# HD301_driver.net
KiCad netlist of a schematic drawn in Altium Designer
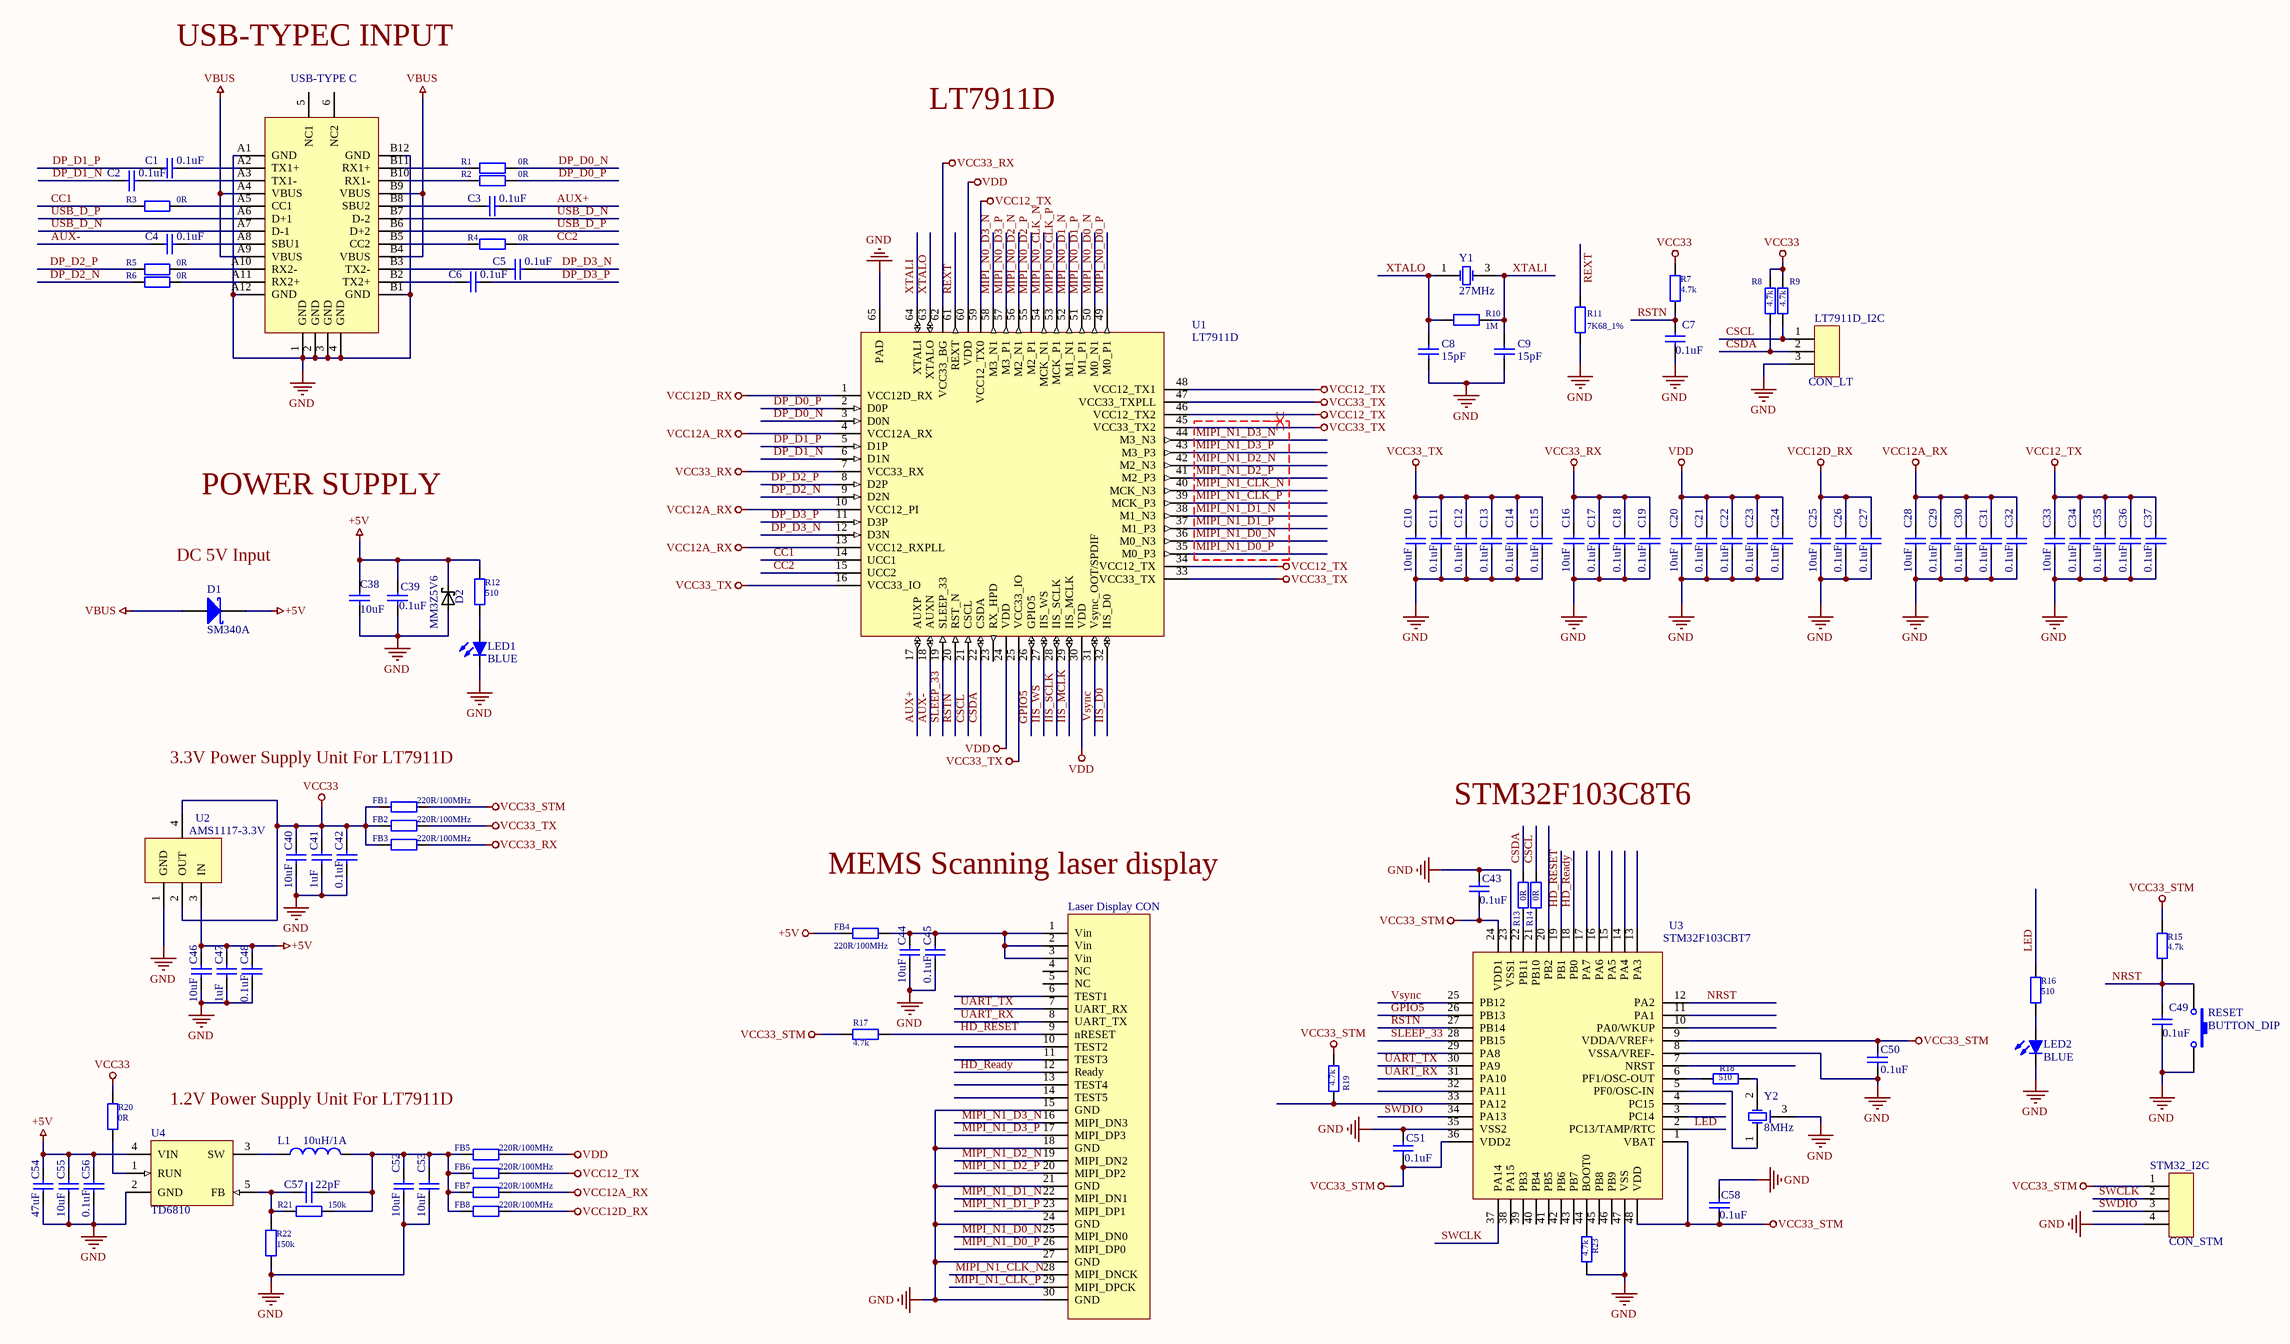
[diagram p0: HD301_driver.SchDoc]

(export (version "E")
  (design (tool "Eeschema 10.0.6"))
  (components
    (comp (ref "C1")
      (value "0.1uF")
      (footprint "0402-C")
      (description "Capacitor")
      (libsource (lib "Miscellaneous Devices") (part "Cap"))
    )
    (comp (ref "C2")
      (value "0.1uF")
      (footprint "0402-C")
      (description "Capacitor")
      (libsource (lib "Miscellaneous Devices") (part "Cap"))
    )
    (comp (ref "C3")
      (value "0.1uF")
      (footprint "0402-C")
      (description "Capacitor")
      (libsource (lib "Miscellaneous Devices") (part "Cap"))
    )
    (comp (ref "C4")
      (value "0.1uF")
      (footprint "0402-C")
      (description "Capacitor")
      (libsource (lib "Miscellaneous Devices") (part "Cap"))
    )
    (comp (ref "C5")
      (value "0.1uF")
      (footprint "0402-C")
      (description "Capacitor")
      (libsource (lib "Miscellaneous Devices") (part "Cap"))
    )
    (comp (ref "C6")
      (value "0.1uF")
      (footprint "0402-C")
      (description "Capacitor")
      (libsource (lib "Miscellaneous Devices") (part "Cap"))
    )
    (comp (ref "C7")
      (value "0.1uF")
      (footprint "0402-C")
      (description "Capacitor")
      (libsource (lib "Miscellaneous Devices") (part "Cap"))
    )
    (comp (ref "C8")
      (value "15pF")
      (footprint "0402-C")
      (description "Capacitor")
      (libsource (lib "Miscellaneous Devices") (part "Cap"))
    )
    (comp (ref "C9")
      (value "15pF")
      (footprint "0402-C")
      (description "Capacitor")
      (libsource (lib "Miscellaneous Devices") (part "Cap"))
    )
    (comp (ref "C10")
      (value "10uF")
      (footprint "0603-C")
      (description "Capacitor")
      (libsource (lib "Miscellaneous Devices") (part "Cap"))
    )
    (comp (ref "C11")
      (value "0.1uF")
      (footprint "0402-C")
      (description "Capacitor")
      (libsource (lib "Miscellaneous Devices") (part "Cap"))
    )
    (comp (ref "C12")
      (value "0.1uF")
      (footprint "0402-C")
      (description "Capacitor")
      (libsource (lib "Miscellaneous Devices") (part "Cap"))
    )
    (comp (ref "C13")
      (value "0.1uF")
      (footprint "0402-C")
      (description "Capacitor")
      (libsource (lib "Miscellaneous Devices") (part "Cap"))
    )
    (comp (ref "C14")
      (value "0.1uF")
      (footprint "0402-C")
      (description "Capacitor")
      (libsource (lib "Miscellaneous Devices") (part "Cap"))
    )
    (comp (ref "C15")
      (value "0.1uF")
      (footprint "0402-C")
      (description "Capacitor")
      (libsource (lib "Miscellaneous Devices") (part "Cap"))
    )
    (comp (ref "C16")
      (value "10uF")
      (footprint "0603-C")
      (description "Capacitor")
      (libsource (lib "Miscellaneous Devices") (part "Cap"))
    )
    (comp (ref "C17")
      (value "0.1uF")
      (footprint "0402-C")
      (description "Capacitor")
      (libsource (lib "Miscellaneous Devices") (part "Cap"))
    )
    (comp (ref "C18")
      (value "0.1uF")
      (footprint "0402-C")
      (description "Capacitor")
      (libsource (lib "Miscellaneous Devices") (part "Cap"))
    )
    (comp (ref "C19")
      (value "0.1uF")
      (footprint "0402-C")
      (description "Capacitor")
      (libsource (lib "Miscellaneous Devices") (part "Cap"))
    )
    (comp (ref "C20")
      (value "10uF")
      (footprint "0603-C")
      (description "Capacitor")
      (libsource (lib "Miscellaneous Devices") (part "Cap"))
    )
    (comp (ref "C21")
      (value "0.1uF")
      (footprint "0402-C")
      (description "Capacitor")
      (libsource (lib "Miscellaneous Devices") (part "Cap"))
    )
    (comp (ref "C22")
      (value "0.1uF")
      (footprint "0402-C")
      (description "Capacitor")
      (libsource (lib "Miscellaneous Devices") (part "Cap"))
    )
    (comp (ref "C23")
      (value "0.1uF")
      (footprint "0402-C")
      (description "Capacitor")
      (libsource (lib "Miscellaneous Devices") (part "Cap"))
    )
    (comp (ref "C24")
      (value "0.1uF")
      (footprint "0402-C")
      (description "Capacitor")
      (libsource (lib "Miscellaneous Devices") (part "Cap"))
    )
    (comp (ref "C25")
      (value "10uF")
      (footprint "0603-C")
      (description "Capacitor")
      (libsource (lib "Miscellaneous Devices") (part "Cap"))
    )
    (comp (ref "C26")
      (value "0.1uF")
      (footprint "0402-C")
      (description "Capacitor")
      (libsource (lib "Miscellaneous Devices") (part "Cap"))
    )
    (comp (ref "C27")
      (value "0.1uF")
      (footprint "0402-C")
      (description "Capacitor")
      (libsource (lib "Miscellaneous Devices") (part "Cap"))
    )
    (comp (ref "C28")
      (value "10uF")
      (footprint "0603-C")
      (description "Capacitor")
      (libsource (lib "Miscellaneous Devices") (part "Cap"))
    )
    (comp (ref "C29")
      (value "0.1uF")
      (footprint "0402-C")
      (description "Capacitor")
      (libsource (lib "Miscellaneous Devices") (part "Cap"))
    )
    (comp (ref "C30")
      (value "0.1uF")
      (footprint "0402-C")
      (description "Capacitor")
      (libsource (lib "Miscellaneous Devices") (part "Cap"))
    )
    (comp (ref "C31")
      (value "0.1uF")
      (footprint "0402-C")
      (description "Capacitor")
      (libsource (lib "Miscellaneous Devices") (part "Cap"))
    )
    (comp (ref "C32")
      (value "0.1uF")
      (footprint "0402-C")
      (description "Capacitor")
      (libsource (lib "Miscellaneous Devices") (part "Cap"))
    )
    (comp (ref "C33")
      (value "10uF")
      (footprint "0603-C")
      (description "Capacitor")
      (libsource (lib "Miscellaneous Devices") (part "Cap"))
    )
    (comp (ref "C34")
      (value "0.1uF")
      (footprint "0402-C")
      (description "Capacitor")
      (libsource (lib "Miscellaneous Devices") (part "Cap"))
    )
    (comp (ref "C35")
      (value "0.1uF")
      (footprint "0402-C")
      (description "Capacitor")
      (libsource (lib "Miscellaneous Devices") (part "Cap"))
    )
    (comp (ref "C36")
      (value "0.1uF")
      (footprint "0402-C")
      (description "Capacitor")
      (libsource (lib "Miscellaneous Devices") (part "Cap"))
    )
    (comp (ref "C37")
      (value "0.1uF")
      (footprint "0402-C")
      (description "Capacitor")
      (libsource (lib "Miscellaneous Devices") (part "Cap"))
    )
    (comp (ref "C38")
      (value "10uF")
      (footprint "0603-C")
      (description "Capacitor")
      (libsource (lib "Miscellaneous Devices") (part "Cap"))
    )
    (comp (ref "C39")
      (value "0.1uF")
      (footprint "0402-C")
      (description "Capacitor")
      (libsource (lib "Miscellaneous Devices") (part "Cap"))
    )
    (comp (ref "C40")
      (value "10uF")
      (footprint "0603-C")
      (description "Capacitor")
      (libsource (lib "Miscellaneous Devices") (part "Cap"))
    )
    (comp (ref "C41")
      (value "1uF")
      (footprint "0603-C")
      (description "Capacitor")
      (libsource (lib "Miscellaneous Devices") (part "Cap"))
    )
    (comp (ref "C42")
      (value "0.1uF")
      (footprint "0402-C")
      (description "Capacitor")
      (libsource (lib "Miscellaneous Devices") (part "Cap"))
    )
    (comp (ref "C43")
      (value "0.1uF")
      (footprint "0402-C")
      (description "Capacitor")
      (libsource (lib "Miscellaneous Devices") (part "Cap"))
    )
    (comp (ref "C44")
      (value "10uF")
      (footprint "0603-C")
      (description "Capacitor")
      (libsource (lib "Miscellaneous Devices") (part "Cap"))
    )
    (comp (ref "C45")
      (value "0.1uF")
      (footprint "0402-C")
      (description "Capacitor")
      (libsource (lib "Miscellaneous Devices") (part "Cap"))
    )
    (comp (ref "C46")
      (value "10uF")
      (footprint "0603-C")
      (description "Capacitor")
      (libsource (lib "Miscellaneous Devices") (part "Cap"))
    )
    (comp (ref "C47")
      (value "1uF")
      (footprint "0603-C")
      (description "Capacitor")
      (libsource (lib "Miscellaneous Devices") (part "Cap"))
    )
    (comp (ref "C48")
      (value "0.1uF")
      (footprint "0402-C")
      (description "Capacitor")
      (libsource (lib "Miscellaneous Devices") (part "Cap"))
    )
    (comp (ref "C49")
      (value "0.1uF")
      (footprint "0402-C")
      (description "Capacitor")
      (libsource (lib "Miscellaneous Devices") (part "Cap"))
    )
    (comp (ref "C50")
      (value "0.1uF")
      (footprint "0402-C")
      (description "Capacitor")
      (libsource (lib "Miscellaneous Devices") (part "Cap"))
    )
    (comp (ref "C51")
      (value "0.1uF")
      (footprint "0402-C")
      (description "Capacitor")
      (libsource (lib "Miscellaneous Devices") (part "Cap"))
    )
    (comp (ref "C52")
      (value "10uF")
      (footprint "0603-C")
      (description "Capacitor")
      (libsource (lib "Miscellaneous Devices") (part "Cap"))
    )
    (comp (ref "C53")
      (value "10uF")
      (footprint "0603-C")
      (description "Capacitor")
      (libsource (lib "Miscellaneous Devices") (part "Cap"))
    )
    (comp (ref "C54")
      (value "47uF")
      (footprint "1206-C")
      (description "Capacitor")
      (libsource (lib "Miscellaneous Devices") (part "Cap"))
    )
    (comp (ref "C55")
      (value "10uF")
      (footprint "0603-C")
      (description "Capacitor")
      (libsource (lib "Miscellaneous Devices") (part "Cap"))
    )
    (comp (ref "C56")
      (value "0.1uF")
      (footprint "0402-C")
      (description "Capacitor")
      (libsource (lib "Miscellaneous Devices") (part "Cap"))
    )
    (comp (ref "C57")
      (value "22pF")
      (footprint "0402-C")
      (description "Capacitor")
      (libsource (lib "Miscellaneous Devices") (part "Cap"))
    )
    (comp (ref "C58")
      (value "0.1uF")
      (footprint "0402-C")
      (description "Capacitor")
      (libsource (lib "Miscellaneous Devices") (part "Cap"))
    )
    (comp (ref "D1")
      (value "SM340A")
      (footprint "SM340A_DO-214AC")
      (description "Schottky Rectifier")
      (libsource (lib "Miscellaneous Devices") (part "Diode 10TQ035"))
    )
    (comp (ref "D2")
      (value "MM3Z5V6")
      (footprint "PDZ_B-SOD323")
      (fields (field (name "MP") "BAT46W") (field (name "MF") "Diotec"))
      (libsource (lib "MySchLib") (part "BAT46W"))
    )
    (comp (ref "FB1")
      (value "220R/100MHz")
      (footprint "0603-FB")
      (description "Resistor")
      (libsource (lib "") (part "Res2_3"))
    )
    (comp (ref "FB2")
      (value "220R/100MHz")
      (footprint "0603-FB")
      (description "Resistor")
      (libsource (lib "") (part "Res2_3"))
    )
    (comp (ref "FB3")
      (value "220R/100MHz")
      (footprint "0603-FB")
      (description "Resistor")
      (libsource (lib "") (part "Res2_3"))
    )
    (comp (ref "FB4")
      (value "220R/100MHz")
      (footprint "0603-FB")
      (description "Resistor")
      (libsource (lib "") (part "Res2_3"))
    )
    (comp (ref "FB5")
      (value "220R/100MHz")
      (footprint "0603-FB")
      (description "Resistor")
      (libsource (lib "") (part "Res2_3"))
    )
    (comp (ref "FB6")
      (value "220R/100MHz")
      (footprint "0603-FB")
      (description "Resistor")
      (libsource (lib "") (part "Res2_3"))
    )
    (comp (ref "FB7")
      (value "220R/100MHz")
      (footprint "0603-FB")
      (description "Resistor")
      (libsource (lib "") (part "Res2_3"))
    )
    (comp (ref "FB8")
      (value "220R/100MHz")
      (footprint "0603-FB")
      (description "Resistor")
      (libsource (lib "") (part "Res2_3"))
    )
    (comp (ref "L1")
      (value "10uH/1A")
      (footprint "Inductor_LPS4018-103MR")
      (description "Inductor")
      (libsource (lib "Miscellaneous Devices") (part "Inductor"))
    )
    (comp (ref "Laser Display CON")
      (value "MIPI-DSI")
      (footprint "50696-030-0-M")
      (libsource (lib "MySchLib") (part "MIPI-DSI"))
    )
    (comp (ref "LED1")
      (value "BLUE")
      (footprint "SMD_LED(0603)")
      (description "Typical RED GaAs LED")
      (libsource (lib "MySchLib") (part "LED1"))
    )
    (comp (ref "LED2")
      (value "BLUE")
      (footprint "SMD_LED(0603)")
      (description "Typical RED GaAs LED")
      (libsource (lib "MySchLib") (part "LED1"))
    )
    (comp (ref "LT7911D_I2C")
      (value "CON_LT")
      (footprint "Header-Female-2.54*3")
      (libsource (lib "MySchLib") (part "3PinConnector"))
    )
    (comp (ref "R1")
      (value "0R")
      (footprint "0402-R")
      (description "Resistor")
      (libsource (lib "") (part "Res2_2"))
    )
    (comp (ref "R2")
      (value "0R")
      (footprint "0402-R")
      (description "Resistor")
      (libsource (lib "") (part "Res2_2"))
    )
    (comp (ref "R3")
      (value "0R")
      (footprint "0402-R")
      (description "Resistor")
      (libsource (lib "") (part "Res2_2"))
    )
    (comp (ref "R4")
      (value "0R")
      (footprint "0402-R")
      (description "Resistor")
      (libsource (lib "") (part "Res2_2"))
    )
    (comp (ref "R5")
      (value "0R")
      (footprint "0402-R")
      (description "Resistor")
      (libsource (lib "") (part "Res2_2"))
    )
    (comp (ref "R6")
      (value "0R")
      (footprint "0402-R")
      (description "Resistor")
      (libsource (lib "") (part "Res2_2"))
    )
    (comp (ref "R7")
      (value "4.7k")
      (footprint "0402-R")
      (description "Resistor")
      (libsource (lib "") (part "Res2_1"))
    )
    (comp (ref "R8")
      (value "4.7k")
      (footprint "0402-R")
      (description "Resistor")
      (libsource (lib "Miscellaneous Devices") (part "Res2"))
    )
    (comp (ref "R9")
      (value "4.7k")
      (footprint "0402-R")
      (description "Resistor")
      (libsource (lib "Miscellaneous Devices") (part "Res2"))
    )
    (comp (ref "R10")
      (value "1M")
      (footprint "0402-R")
      (description "Resistor")
      (libsource (lib "") (part "Res2_3"))
    )
    (comp (ref "R11")
      (value "7K68_1%")
      (footprint "0402-R")
      (description "Resistor")
      (libsource (lib "Miscellaneous Devices") (part "Res2"))
    )
    (comp (ref "R12")
      (value "510")
      (footprint "0402-R")
      (description "Resistor")
      (libsource (lib "") (part "Res2_1"))
    )
    (comp (ref "R13")
      (value "0R")
      (footprint "0402-R")
      (description "Resistor")
      (libsource (lib "Miscellaneous Devices") (part "Res2"))
    )
    (comp (ref "R14")
      (value "0R")
      (footprint "0402-R")
      (description "Resistor")
      (libsource (lib "Miscellaneous Devices") (part "Res2"))
    )
    (comp (ref "R15")
      (value "4.7k")
      (footprint "0402-R")
      (description "Resistor")
      (libsource (lib "") (part "Res2_1"))
    )
    (comp (ref "R16")
      (value "510")
      (footprint "0402-R")
      (description "Resistor")
      (libsource (lib "") (part "Res2_1"))
    )
    (comp (ref "R17")
      (value "4.7k")
      (footprint "0402-R")
      (description "Resistor")
      (libsource (lib "") (part "Res2_2"))
    )
    (comp (ref "R18")
      (value "510")
      (footprint "0402-R")
      (description "Resistor")
      (libsource (lib "") (part "Res2_3"))
    )
    (comp (ref "R19")
      (value "4.7k")
      (footprint "0402-R")
      (description "Resistor")
      (libsource (lib "Miscellaneous Devices") (part "Res2"))
    )
    (comp (ref "R20")
      (value "0R")
      (footprint "0402-R")
      (description "Resistor")
      (libsource (lib "") (part "Res2_1"))
    )
    (comp (ref "R21")
      (value "150k")
      (footprint "0402-R")
      (description "Resistor")
      (libsource (lib "") (part "Res2_3"))
    )
    (comp (ref "R22")
      (value "150k")
      (footprint "0402-R")
      (description "Resistor")
      (libsource (lib "Miscellaneous Devices") (part "Res2"))
    )
    (comp (ref "R23")
      (value "4.7k")
      (footprint "0402-R")
      (description "Resistor")
      (libsource (lib "Miscellaneous Devices") (part "Res2"))
    )
    (comp (ref "RESET")
      (value "BUTTON_DIP")
      (footprint "Push button_mini(2 pin)")
      (description "Switch")
      (libsource (lib "Miscellaneous Devices") (part "SW-PB"))
    )
    (comp (ref "STM32_I2C")
      (value "CON_STM")
      (footprint "Header-Female-2.54*4")
      (libsource (lib "MySchLib") (part "4PinConnector"))
    )
    (comp (ref "U1")
      (value "LT7911D")
      (footprint "QFN64_EPAD")
      (description "USB/MIPI port converter")
      (libsource (lib "MySchLib") (part "LT7911D"))
    )
    (comp (ref "U2")
      (value "AMS1117-3.3V")
      (footprint "AMS1117_SOT-223_4")
      (description "3.3V Voltage Regulator")
      (libsource (lib "MySchLib") (part "AMS1117-3.3V"))
    )
    (comp (ref "U3")
      (value "STM32F103CBT7")
      (footprint "LQFP48-7mm*7mm")
      (description "32bit MCU")
      (libsource (lib "MySchLib") (part "STM32F303CBT7"))
    )
    (comp (ref "U4")
      (value "TD6810")
      (footprint "TD6810_SOT23-5")
      (description "voltage regulater")
      (libsource (lib "MySchLib") (part "TD6810"))
    )
    (comp (ref "USB-TYPE C")
      (value "USB-TYPEC")
      (footprint "USB_TYPEC_RECEPTACLE_DIP")
      (description "USB-TYPEC INPUT")
      (libsource (lib "MySchLib") (part "USB-TYPEC"))
    )
    (comp (ref "Y1")
      (value "27MHz")
      (footprint "CRY_3225")
      (description "Crystal Oscillator")
      (libsource (lib "MySchLib") (part "XTAL_2"))
    )
    (comp (ref "Y2")
      (value "8MHz")
      (footprint "Resonator_mini")
      (description "Crystal Oscillator")
      (libsource (lib "MySchLib") (part "XTAL"))
    )
  )
  (nets
    (net (code "1") (name "+5V") (class "Default")
      (node (ref "C38") (pin "1") (pinfunction "1_1") (pintype "passive"))
      (node (ref "C39") (pin "2") (pinfunction "2_2") (pintype "passive"))
      (node (ref "C46") (pin "1") (pinfunction "1_1") (pintype "passive"))
      (node (ref "C47") (pin "1") (pinfunction "1_1") (pintype "passive"))
      (node (ref "C48") (pin "1") (pinfunction "1_1") (pintype "passive"))
      (node (ref "C54") (pin "1") (pinfunction "1_1") (pintype "passive"))
      (node (ref "C55") (pin "1") (pinfunction "1_1") (pintype "passive"))
      (node (ref "C56") (pin "1") (pinfunction "1_1") (pintype "passive"))
      (node (ref "D1") (pin "C") (pinfunction "C_C") (pintype "passive"))
      (node (ref "D2") (pin "C") (pinfunction "C_C") (pintype "passive"))
      (node (ref "FB4") (pin "1") (pinfunction "1_1") (pintype "passive"))
      (node (ref "R12") (pin "1") (pinfunction "1_1") (pintype "passive"))
      (node (ref "U2") (pin "3") (pinfunction "IN_3") (pintype "passive"))
      (node (ref "U4") (pin "4") (pinfunction "VIN_4") (pintype "passive"))
    )
    (net (code "2") (name "/AUX+") (class "Default")
      (node (ref "C3") (pin "2") (pinfunction "2_2") (pintype "passive"))
      (node (ref "U1") (pin "17") (pinfunction "AUXP_17") (pintype "bidirectional"))
    )
    (net (code "3") (name "/AUX-") (class "Default")
      (node (ref "C4") (pin "2") (pinfunction "2_2") (pintype "passive"))
      (node (ref "U1") (pin "18") (pinfunction "AUXN_18") (pintype "bidirectional"))
    )
    (net (code "4") (name "/CC1") (class "Default")
      (node (ref "R3") (pin "2") (pinfunction "2_2") (pintype "passive"))
      (node (ref "U1") (pin "14") (pinfunction "UCC1_14") (pintype "power_in"))
    )
    (net (code "5") (name "/CC2") (class "Default")
      (node (ref "R4") (pin "1") (pinfunction "1_1") (pintype "passive"))
      (node (ref "U1") (pin "15") (pinfunction "UCC2_15") (pintype "power_in"))
    )
    (net (code "6") (name "/CSCL") (class "Default")
      (node (ref "LT7911D_I2C") (pin "1") (pinfunction "1_1") (pintype "passive"))
      (node (ref "R14") (pin "2") (pinfunction "2_2") (pintype "passive"))
      (node (ref "R9") (pin "1") (pinfunction "1_1") (pintype "passive"))
      (node (ref "U1") (pin "21") (pinfunction "CSCL_21") (pintype "input"))
    )
    (net (code "7") (name "/CSDA") (class "Default")
      (node (ref "LT7911D_I2C") (pin "2") (pinfunction "2_2") (pintype "passive"))
      (node (ref "R13") (pin "2") (pinfunction "2_2") (pintype "passive"))
      (node (ref "R8") (pin "1") (pinfunction "1_1") (pintype "passive"))
      (node (ref "U1") (pin "22") (pinfunction "CSDA_22") (pintype "bidirectional"))
    )
    (net (code "8") (name "/DP_D0_N") (class "Default")
      (node (ref "R1") (pin "1") (pinfunction "1_1") (pintype "passive"))
      (node (ref "U1") (pin "3") (pinfunction "D0N_3") (pintype "input"))
    )
    (net (code "9") (name "/DP_D0_P") (class "Default")
      (node (ref "R2") (pin "1") (pinfunction "1_1") (pintype "passive"))
      (node (ref "U1") (pin "2") (pinfunction "D0P_2") (pintype "input"))
    )
    (net (code "10") (name "/DP_D1_N") (class "Default")
      (node (ref "C2") (pin "2") (pinfunction "2_2") (pintype "passive"))
      (node (ref "U1") (pin "6") (pinfunction "D1N_6") (pintype "input"))
    )
    (net (code "11") (name "/DP_D1_P") (class "Default")
      (node (ref "C1") (pin "2") (pinfunction "2_2") (pintype "passive"))
      (node (ref "U1") (pin "5") (pinfunction "D1P_5") (pintype "input"))
    )
    (net (code "12") (name "/DP_D2_N") (class "Default")
      (node (ref "R6") (pin "2") (pinfunction "2_2") (pintype "passive"))
      (node (ref "U1") (pin "9") (pinfunction "D2N_9") (pintype "input"))
    )
    (net (code "13") (name "/DP_D2_P") (class "Default")
      (node (ref "R5") (pin "2") (pinfunction "2_2") (pintype "passive"))
      (node (ref "U1") (pin "8") (pinfunction "D2P_8") (pintype "input"))
    )
    (net (code "14") (name "/DP_D3_N") (class "Default")
      (node (ref "C5") (pin "2") (pinfunction "2_2") (pintype "passive"))
      (node (ref "U1") (pin "12") (pinfunction "D3N_12") (pintype "input"))
    )
    (net (code "15") (name "/DP_D3_P") (class "Default")
      (node (ref "C6") (pin "2") (pinfunction "2_2") (pintype "passive"))
      (node (ref "U1") (pin "11") (pinfunction "D3P_11") (pintype "input"))
    )
    (net (code "16") (name "/GPIO5") (class "Default")
      (node (ref "U1") (pin "26") (pinfunction "GPIO5_26") (pintype "bidirectional"))
      (node (ref "U3") (pin "26") (pinfunction "PB13_26") (pintype "power_in"))
    )
    (net (code "17") (name "/HD_RESET") (class "Default")
      (node (ref "Laser Display CON") (pin "9") (pinfunction "nRESET_9") (pintype "passive"))
      (node (ref "R17") (pin "1") (pinfunction "1_1") (pintype "passive"))
      (node (ref "U3") (pin "19") (pinfunction "PB1_19") (pintype "power_in"))
    )
    (net (code "18") (name "/HD_Ready") (class "Default")
      (node (ref "Laser Display CON") (pin "12") (pinfunction "Ready_12") (pintype "passive"))
      (node (ref "U3") (pin "18") (pinfunction "PB0_18") (pintype "power_in"))
    )
    (net (code "19") (name "/IIS_D0") (class "Default")
      (node (ref "U1") (pin "32") (pinfunction "IIS_D0_32") (pintype "bidirectional"))
    )
    (net (code "20") (name "/IIS_MCLK") (class "Default")
      (node (ref "U1") (pin "29") (pinfunction "IIS_MCLK_29") (pintype "bidirectional"))
    )
    (net (code "21") (name "/IIS_SCLK") (class "Default")
      (node (ref "U1") (pin "28") (pinfunction "IIS_SCLK_28") (pintype "bidirectional"))
    )
    (net (code "22") (name "/IIS_WS") (class "Default")
      (node (ref "U1") (pin "27") (pinfunction "IIS_WS_27") (pintype "bidirectional"))
    )
    (net (code "23") (name "/LED") (class "Default")
      (node (ref "R16") (pin "1") (pinfunction "1_1") (pintype "passive"))
      (node (ref "U3") (pin "2") (pinfunction "PC13/TAMP/RTC_2") (pintype "power_in"))
    )
    (net (code "24") (name "/MIPI_N0_CLK_N") (class "Default")
      (node (ref "U1") (pin "54") (pinfunction "MCK_N1_54") (pintype "output"))
    )
    (net (code "25") (name "/MIPI_N0_CLK_P") (class "Default")
      (node (ref "U1") (pin "53") (pinfunction "MCK_P1_53") (pintype "output"))
    )
    (net (code "26") (name "/MIPI_N0_D0_N") (class "Default")
      (node (ref "U1") (pin "50") (pinfunction "M0_N1_50") (pintype "output"))
    )
    (net (code "27") (name "/MIPI_N0_D0_P") (class "Default")
      (node (ref "U1") (pin "49") (pinfunction "M0_P1_49") (pintype "output"))
    )
    (net (code "28") (name "/MIPI_N0_D1_N") (class "Default")
      (node (ref "U1") (pin "52") (pinfunction "M1_N1_52") (pintype "output"))
    )
    (net (code "29") (name "/MIPI_N0_D1_P") (class "Default")
      (node (ref "U1") (pin "51") (pinfunction "M1_P1_51") (pintype "output"))
    )
    (net (code "30") (name "/MIPI_N0_D2_N") (class "Default")
      (node (ref "U1") (pin "56") (pinfunction "M2_N1_56") (pintype "output"))
    )
    (net (code "31") (name "/MIPI_N0_D2_P") (class "Default")
      (node (ref "U1") (pin "55") (pinfunction "M2_P1_55") (pintype "open_collector"))
    )
    (net (code "32") (name "/MIPI_N0_D3_N") (class "Default")
      (node (ref "U1") (pin "58") (pinfunction "M3_N1_58") (pintype "output"))
    )
    (net (code "33") (name "/MIPI_N0_D3_P") (class "Default")
      (node (ref "U1") (pin "57") (pinfunction "M3_P1_57") (pintype "output"))
    )
    (net (code "34") (name "/MIPI_N1_CLK_N") (class "Default")
      (node (ref "Laser Display CON") (pin "28") (pinfunction "MIPI_DNCK_28") (pintype "passive"))
      (node (ref "U1") (pin "40") (pinfunction "MCK_N3_40") (pintype "output"))
    )
    (net (code "35") (name "/MIPI_N1_CLK_P") (class "Default")
      (node (ref "Laser Display CON") (pin "29") (pinfunction "MIPI_DPCK_29") (pintype "passive"))
      (node (ref "U1") (pin "39") (pinfunction "MCK_P3_39") (pintype "output"))
    )
    (net (code "36") (name "/MIPI_N1_D0_N") (class "Default")
      (node (ref "Laser Display CON") (pin "25") (pinfunction "MIPI_DN0_25") (pintype "passive"))
      (node (ref "U1") (pin "36") (pinfunction "M0_N3_36") (pintype "output"))
    )
    (net (code "37") (name "/MIPI_N1_D0_P") (class "Default")
      (node (ref "Laser Display CON") (pin "26") (pinfunction "MIPI_DP0_26") (pintype "passive"))
      (node (ref "U1") (pin "35") (pinfunction "M0_P3_35") (pintype "output"))
    )
    (net (code "38") (name "/MIPI_N1_D1_N") (class "Default")
      (node (ref "Laser Display CON") (pin "22") (pinfunction "MIPI_DN1_22") (pintype "passive"))
      (node (ref "U1") (pin "38") (pinfunction "M1_N3_38") (pintype "output"))
    )
    (net (code "39") (name "/MIPI_N1_D1_P") (class "Default")
      (node (ref "Laser Display CON") (pin "23") (pinfunction "MIPI_DP1_23") (pintype "passive"))
      (node (ref "U1") (pin "37") (pinfunction "M1_P3_37") (pintype "output"))
    )
    (net (code "40") (name "/MIPI_N1_D2_N") (class "Default")
      (node (ref "Laser Display CON") (pin "19") (pinfunction "MIPI_DN2_19") (pintype "passive"))
      (node (ref "U1") (pin "42") (pinfunction "M2_N3_42") (pintype "output"))
    )
    (net (code "41") (name "/MIPI_N1_D2_P") (class "Default")
      (node (ref "Laser Display CON") (pin "20") (pinfunction "MIPI_DP2_20") (pintype "passive"))
      (node (ref "U1") (pin "41") (pinfunction "M2_P3_41") (pintype "output"))
    )
    (net (code "42") (name "/MIPI_N1_D3_N") (class "Default")
      (node (ref "Laser Display CON") (pin "16") (pinfunction "MIPI_DN3_16") (pintype "passive"))
      (node (ref "U1") (pin "44") (pinfunction "M3_N3_44") (pintype "output"))
    )
    (net (code "43") (name "/MIPI_N1_D3_P") (class "Default")
      (node (ref "Laser Display CON") (pin "17") (pinfunction "MIPI_DP3_17") (pintype "passive"))
      (node (ref "U1") (pin "43") (pinfunction "M3_P3_43") (pintype "output"))
    )
    (net (code "44") (name "/NRST") (class "Default")
      (node (ref "C49") (pin "1") (pinfunction "1_1") (pintype "passive"))
      (node (ref "R15") (pin "2") (pinfunction "2_2") (pintype "passive"))
      (node (ref "RESET") (pin "1") (pinfunction "1_1") (pintype "passive"))
      (node (ref "U3") (pin "12") (pinfunction "PA2_12") (pintype "power_in"))
    )
    (net (code "45") (name "/REXT") (class "Default")
      (node (ref "R11") (pin "2") (pinfunction "2_2") (pintype "passive"))
      (node (ref "U1") (pin "61") (pinfunction "REXT_61") (pintype "output"))
    )
    (net (code "46") (name "/RSTN") (class "Default")
      (node (ref "C7") (pin "1") (pinfunction "1_1") (pintype "passive"))
      (node (ref "R7") (pin "2") (pinfunction "2_2") (pintype "passive"))
      (node (ref "U1") (pin "20") (pinfunction "RST_N_20") (pintype "input"))
      (node (ref "U3") (pin "27") (pinfunction "PB14_27") (pintype "power_in"))
    )
    (net (code "47") (name "/SLEEP_33") (class "Default")
      (node (ref "U1") (pin "19") (pinfunction "SLEEP_33_19") (pintype "input"))
      (node (ref "U3") (pin "28") (pinfunction "PB15_28") (pintype "power_in"))
    )
    (net (code "48") (name "/SWCLK") (class "Default")
      (node (ref "STM32_I2C") (pin "2") (pinfunction "2_2") (pintype "passive"))
      (node (ref "U3") (pin "37") (pinfunction "PA14_37") (pintype "power_in"))
    )
    (net (code "49") (name "/SWDIO") (class "Default")
      (node (ref "STM32_I2C") (pin "3") (pinfunction "3_3") (pintype "passive"))
      (node (ref "U3") (pin "34") (pinfunction "PA13_34") (pintype "power_in"))
    )
    (net (code "50") (name "/UART_RX") (class "Default")
      (node (ref "Laser Display CON") (pin "8") (pinfunction "UART_TX_8") (pintype "passive"))
      (node (ref "U3") (pin "31") (pinfunction "PA10_31") (pintype "power_in"))
    )
    (net (code "51") (name "/UART_TX") (class "Default")
      (node (ref "Laser Display CON") (pin "7") (pinfunction "UART_RX_7") (pintype "passive"))
      (node (ref "U3") (pin "30") (pinfunction "PA9_30") (pintype "power_in"))
    )
    (net (code "52") (name "/USB_D_N") (class "Default")
      (node (ref "USB-TYPE C") (pin "A7") (pinfunction "D-1_A7") (pintype "passive"))
      (node (ref "USB-TYPE C") (pin "B7") (pinfunction "D-2_B7") (pintype "passive"))
    )
    (net (code "53") (name "/USB_D_P") (class "Default")
      (node (ref "USB-TYPE C") (pin "A6") (pinfunction "D+1_A6") (pintype "passive"))
      (node (ref "USB-TYPE C") (pin "B6") (pinfunction "D+2_B6") (pintype "passive"))
    )
    (net (code "54") (name "/Vsync") (class "Default")
      (node (ref "U1") (pin "31") (pinfunction "Vsync_OOT/SPDIF_31") (pintype "bidirectional"))
      (node (ref "U3") (pin "25") (pinfunction "PB12_25") (pintype "power_in"))
    )
    (net (code "55") (name "/XTALI") (class "Default")
      (node (ref "C9") (pin "1") (pinfunction "1_1") (pintype "passive"))
      (node (ref "R10") (pin "2") (pinfunction "2_2") (pintype "passive"))
      (node (ref "U1") (pin "64") (pinfunction "XTALI_64") (pintype "bidirectional"))
      (node (ref "Y1") (pin "3") (pinfunction "OSC2_3") (pintype "passive"))
    )
    (net (code "56") (name "/XTALO") (class "Default")
      (node (ref "C8") (pin "1") (pinfunction "1_1") (pintype "passive"))
      (node (ref "R10") (pin "1") (pinfunction "1_1") (pintype "passive"))
      (node (ref "U1") (pin "63") (pinfunction "XTALO_63") (pintype "bidirectional"))
      (node (ref "Y1") (pin "1") (pinfunction "OSC1_1") (pintype "passive"))
    )
    (net (code "57") (name "GND") (class "Default")
      (node (ref "C10") (pin "2") (pinfunction "2_2") (pintype "passive"))
      (node (ref "C11") (pin "2") (pinfunction "2_2") (pintype "passive"))
      (node (ref "C12") (pin "2") (pinfunction "2_2") (pintype "passive"))
      (node (ref "C13") (pin "2") (pinfunction "2_2") (pintype "passive"))
      (node (ref "C14") (pin "2") (pinfunction "2_2") (pintype "passive"))
      (node (ref "C15") (pin "2") (pinfunction "2_2") (pintype "passive"))
      (node (ref "C16") (pin "2") (pinfunction "2_2") (pintype "passive"))
      (node (ref "C17") (pin "2") (pinfunction "2_2") (pintype "passive"))
      (node (ref "C18") (pin "2") (pinfunction "2_2") (pintype "passive"))
      (node (ref "C19") (pin "2") (pinfunction "2_2") (pintype "passive"))
      (node (ref "C20") (pin "2") (pinfunction "2_2") (pintype "passive"))
      (node (ref "C21") (pin "2") (pinfunction "2_2") (pintype "passive"))
      (node (ref "C22") (pin "2") (pinfunction "2_2") (pintype "passive"))
      (node (ref "C23") (pin "2") (pinfunction "2_2") (pintype "passive"))
      (node (ref "C24") (pin "2") (pinfunction "2_2") (pintype "passive"))
      (node (ref "C25") (pin "2") (pinfunction "2_2") (pintype "passive"))
      (node (ref "C26") (pin "2") (pinfunction "2_2") (pintype "passive"))
      (node (ref "C27") (pin "2") (pinfunction "2_2") (pintype "passive"))
      (node (ref "C28") (pin "2") (pinfunction "2_2") (pintype "passive"))
      (node (ref "C29") (pin "2") (pinfunction "2_2") (pintype "passive"))
      (node (ref "C30") (pin "2") (pinfunction "2_2") (pintype "passive"))
      (node (ref "C31") (pin "2") (pinfunction "2_2") (pintype "passive"))
      (node (ref "C32") (pin "2") (pinfunction "2_2") (pintype "passive"))
      (node (ref "C33") (pin "2") (pinfunction "2_2") (pintype "passive"))
      (node (ref "C34") (pin "2") (pinfunction "2_2") (pintype "passive"))
      (node (ref "C35") (pin "2") (pinfunction "2_2") (pintype "passive"))
      (node (ref "C36") (pin "2") (pinfunction "2_2") (pintype "passive"))
      (node (ref "C37") (pin "2") (pinfunction "2_2") (pintype "passive"))
      (node (ref "C38") (pin "2") (pinfunction "2_2") (pintype "passive"))
      (node (ref "C39") (pin "1") (pinfunction "1_1") (pintype "passive"))
      (node (ref "C40") (pin "2") (pinfunction "2_2") (pintype "passive"))
      (node (ref "C41") (pin "2") (pinfunction "2_2") (pintype "passive"))
      (node (ref "C42") (pin "2") (pinfunction "2_2") (pintype "passive"))
      (node (ref "C43") (pin "2") (pinfunction "2_2") (pintype "passive"))
      (node (ref "C44") (pin "2") (pinfunction "2_2") (pintype "passive"))
      (node (ref "C45") (pin "2") (pinfunction "2_2") (pintype "passive"))
      (node (ref "C46") (pin "2") (pinfunction "2_2") (pintype "passive"))
      (node (ref "C47") (pin "2") (pinfunction "2_2") (pintype "passive"))
      (node (ref "C48") (pin "2") (pinfunction "2_2") (pintype "passive"))
      (node (ref "C49") (pin "2") (pinfunction "2_2") (pintype "passive"))
      (node (ref "C50") (pin "1") (pinfunction "1_1") (pintype "passive"))
      (node (ref "C51") (pin "2") (pinfunction "2_2") (pintype "passive"))
      (node (ref "C52") (pin "2") (pinfunction "2_2") (pintype "passive"))
      (node (ref "C53") (pin "2") (pinfunction "2_2") (pintype "passive"))
      (node (ref "C54") (pin "2") (pinfunction "2_2") (pintype "passive"))
      (node (ref "C55") (pin "2") (pinfunction "2_2") (pintype "passive"))
      (node (ref "C56") (pin "2") (pinfunction "2_2") (pintype "passive"))
      (node (ref "C58") (pin "2") (pinfunction "2_2") (pintype "passive"))
      (node (ref "C7") (pin "2") (pinfunction "2_2") (pintype "passive"))
      (node (ref "C8") (pin "2") (pinfunction "2_2") (pintype "passive"))
      (node (ref "C9") (pin "2") (pinfunction "2_2") (pintype "passive"))
      (node (ref "D2") (pin "A") (pinfunction "A_A") (pintype "passive"))
      (node (ref "LED1") (pin "2") (pinfunction "K_2") (pintype "passive"))
      (node (ref "LED2") (pin "2") (pinfunction "K_2") (pintype "passive"))
      (node (ref "LT7911D_I2C") (pin "3") (pinfunction "3_3") (pintype "passive"))
      (node (ref "Laser Display CON") (pin "15") (pinfunction "GND_15") (pintype "passive"))
      (node (ref "Laser Display CON") (pin "18") (pinfunction "GND_18") (pintype "passive"))
      (node (ref "Laser Display CON") (pin "21") (pinfunction "GND_21") (pintype "passive"))
      (node (ref "Laser Display CON") (pin "24") (pinfunction "GND_24") (pintype "passive"))
      (node (ref "Laser Display CON") (pin "27") (pinfunction "GND_27") (pintype "passive"))
      (node (ref "Laser Display CON") (pin "30") (pinfunction "GND_30") (pintype "passive"))
      (node (ref "R11") (pin "1") (pinfunction "1_1") (pintype "passive"))
      (node (ref "R22") (pin "1") (pinfunction "1_1") (pintype "passive"))
      (node (ref "R23") (pin "1") (pinfunction "1_1") (pintype "passive"))
      (node (ref "RESET") (pin "2") (pinfunction "2_2") (pintype "passive"))
      (node (ref "STM32_I2C") (pin "4") (pinfunction "4_4") (pintype "passive"))
      (node (ref "U1") (pin "65") (pinfunction "PAD_65") (pintype "power_in"))
      (node (ref "U2") (pin "1") (pinfunction "GND_1") (pintype "passive"))
      (node (ref "U3") (pin "23") (pinfunction "VSS1_23") (pintype "power_in"))
      (node (ref "U3") (pin "35") (pinfunction "VSS2_35") (pintype "power_in"))
      (node (ref "U3") (pin "47") (pinfunction "VSS_47") (pintype "power_in"))
      (node (ref "U3") (pin "8") (pinfunction "VSSA/VREF-_8") (pintype "power_in"))
      (node (ref "U4") (pin "2") (pinfunction "GND_2") (pintype "passive"))
      (node (ref "USB-TYPE C") (pin "1") (pinfunction "GND_1") (pintype "passive"))
      (node (ref "USB-TYPE C") (pin "2") (pinfunction "GND_2") (pintype "passive"))
      (node (ref "USB-TYPE C") (pin "3") (pinfunction "GND_3") (pintype "passive"))
      (node (ref "USB-TYPE C") (pin "4") (pinfunction "GND_4") (pintype "passive"))
      (node (ref "USB-TYPE C") (pin "A1") (pinfunction "GND_A1") (pintype "passive"))
      (node (ref "USB-TYPE C") (pin "A12") (pinfunction "GND_A12") (pintype "passive"))
      (node (ref "USB-TYPE C") (pin "B1") (pinfunction "GND_B1") (pintype "passive"))
      (node (ref "USB-TYPE C") (pin "B12") (pinfunction "GND_B12") (pintype "passive"))
      (node (ref "Y2") (pin "3") (pinfunction "OSC2_3") (pintype "passive"))
    )
    (net (code "58") (name "Net-(C44-Pad1)") (class "Default")
      (node (ref "C44") (pin "1") (pinfunction "1_1") (pintype "passive"))
      (node (ref "C45") (pin "1") (pinfunction "1_1") (pintype "passive"))
      (node (ref "FB4") (pin "2") (pinfunction "2_2") (pintype "passive"))
      (node (ref "Laser Display CON") (pin "1") (pinfunction "Vin_1") (pintype "passive"))
      (node (ref "Laser Display CON") (pin "2") (pinfunction "Vin_2") (pintype "passive"))
      (node (ref "Laser Display CON") (pin "3") (pinfunction "Vin_3") (pintype "passive"))
    )
    (net (code "59") (name "Net-(C52-Pad1)") (class "Default")
      (node (ref "C52") (pin "1") (pinfunction "1_1") (pintype "passive"))
      (node (ref "C53") (pin "1") (pinfunction "1_1") (pintype "passive"))
      (node (ref "C57") (pin "2") (pinfunction "2_2") (pintype "passive"))
      (node (ref "FB5") (pin "1") (pinfunction "1_1") (pintype "passive"))
      (node (ref "FB6") (pin "1") (pinfunction "1_1") (pintype "passive"))
      (node (ref "FB7") (pin "1") (pinfunction "1_1") (pintype "passive"))
      (node (ref "FB8") (pin "1") (pinfunction "1_1") (pintype "passive"))
      (node (ref "L1") (pin "2") (pinfunction "2_2") (pintype "passive"))
      (node (ref "R21") (pin "2") (pinfunction "2_2") (pintype "passive"))
    )
    (net (code "60") (name "Net-(LED1-A)") (class "Default")
      (node (ref "LED1") (pin "1") (pinfunction "A_1") (pintype "passive"))
      (node (ref "R12") (pin "2") (pinfunction "2_2") (pintype "passive"))
    )
    (net (code "61") (name "Net-(LED2-A)") (class "Default")
      (node (ref "LED2") (pin "1") (pinfunction "A_1") (pintype "passive"))
      (node (ref "R16") (pin "2") (pinfunction "2_2") (pintype "passive"))
    )
    (net (code "62") (name "Net-(R18-Pad2)") (class "Default")
      (node (ref "R18") (pin "2") (pinfunction "2_2") (pintype "passive"))
      (node (ref "Y2") (pin "2") (pinfunction "OSC2_2") (pintype "passive"))
    )
    (net (code "63") (name "Net-(U3-BOOT0)") (class "Default")
      (node (ref "R23") (pin "2") (pinfunction "2_2") (pintype "passive"))
      (node (ref "U3") (pin "44") (pinfunction "BOOT0_44") (pintype "power_in"))
    )
    (net (code "64") (name "Net-(U3-PA12)") (class "Default")
      (node (ref "R19") (pin "1") (pinfunction "1_1") (pintype "passive"))
      (node (ref "U3") (pin "33") (pinfunction "PA12_33") (pintype "power_in"))
    )
    (net (code "65") (name "Net-(U3-PB10)") (class "Default")
      (node (ref "R14") (pin "1") (pinfunction "1_1") (pintype "passive"))
      (node (ref "U3") (pin "21") (pinfunction "PB10_21") (pintype "power_in"))
    )
    (net (code "66") (name "Net-(U3-PB11)") (class "Default")
      (node (ref "R13") (pin "1") (pinfunction "1_1") (pintype "passive"))
      (node (ref "U3") (pin "22") (pinfunction "PB11_22") (pintype "power_in"))
    )
    (net (code "67") (name "Net-(U3-PF0{slash}OSC-IN)") (class "Default")
      (node (ref "U3") (pin "5") (pinfunction "PF0/OSC-IN_5") (pintype "power_in"))
      (node (ref "Y2") (pin "1") (pinfunction "OSC1_1") (pintype "passive"))
    )
    (net (code "68") (name "Net-(U3-PF1{slash}OSC-OUT)") (class "Default")
      (node (ref "R18") (pin "1") (pinfunction "1_1") (pintype "passive"))
      (node (ref "U3") (pin "6") (pinfunction "PF1/OSC-OUT_6") (pintype "power_in"))
    )
    (net (code "69") (name "Net-(U4-FB)") (class "Default")
      (node (ref "C57") (pin "1") (pinfunction "1_1") (pintype "passive"))
      (node (ref "R21") (pin "1") (pinfunction "1_1") (pintype "passive"))
      (node (ref "R22") (pin "2") (pinfunction "2_2") (pintype "passive"))
      (node (ref "U4") (pin "5") (pinfunction "FB_5") (pintype "input"))
    )
    (net (code "70") (name "Net-(U4-RUN)") (class "Default")
      (node (ref "R20") (pin "2") (pinfunction "2_2") (pintype "passive"))
      (node (ref "U4") (pin "1") (pinfunction "RUN_1") (pintype "input"))
    )
    (net (code "71") (name "Net-(U4-SW)") (class "Default")
      (node (ref "L1") (pin "1") (pinfunction "1_1") (pintype "passive"))
      (node (ref "U4") (pin "3") (pinfunction "SW_3") (pintype "passive"))
    )
    (net (code "72") (name "Net-(USB-TYPE C-CC1)") (class "Default")
      (node (ref "R3") (pin "1") (pinfunction "1_1") (pintype "passive"))
      (node (ref "USB-TYPE C") (pin "A5") (pinfunction "CC1_A5") (pintype "passive"))
    )
    (net (code "73") (name "Net-(USB-TYPE C-CC2)") (class "Default")
      (node (ref "R4") (pin "2") (pinfunction "2_2") (pintype "passive"))
      (node (ref "USB-TYPE C") (pin "B5") (pinfunction "CC2_B5") (pintype "passive"))
    )
    (net (code "74") (name "Net-(USB-TYPE C-RX1+)") (class "Default")
      (node (ref "R1") (pin "2") (pinfunction "2_2") (pintype "passive"))
      (node (ref "USB-TYPE C") (pin "B11") (pinfunction "RX1+_B11") (pintype "passive"))
    )
    (net (code "75") (name "Net-(USB-TYPE C-RX1-)") (class "Default")
      (node (ref "R2") (pin "2") (pinfunction "2_2") (pintype "passive"))
      (node (ref "USB-TYPE C") (pin "B10") (pinfunction "RX1-_B10") (pintype "passive"))
    )
    (net (code "76") (name "Net-(USB-TYPE C-RX2+)") (class "Default")
      (node (ref "R6") (pin "1") (pinfunction "1_1") (pintype "passive"))
      (node (ref "USB-TYPE C") (pin "A11") (pinfunction "RX2+_A11") (pintype "passive"))
    )
    (net (code "77") (name "Net-(USB-TYPE C-RX2-)") (class "Default")
      (node (ref "R5") (pin "1") (pinfunction "1_1") (pintype "passive"))
      (node (ref "USB-TYPE C") (pin "A10") (pinfunction "RX2-_A10") (pintype "passive"))
    )
    (net (code "78") (name "Net-(USB-TYPE C-SBU1)") (class "Default")
      (node (ref "C4") (pin "1") (pinfunction "1_1") (pintype "passive"))
      (node (ref "USB-TYPE C") (pin "A8") (pinfunction "SBU1_A8") (pintype "passive"))
    )
    (net (code "79") (name "Net-(USB-TYPE C-SBU2)") (class "Default")
      (node (ref "C3") (pin "1") (pinfunction "1_1") (pintype "passive"))
      (node (ref "USB-TYPE C") (pin "B8") (pinfunction "SBU2_B8") (pintype "passive"))
    )
    (net (code "80") (name "Net-(USB-TYPE C-TX1+)") (class "Default")
      (node (ref "C1") (pin "1") (pinfunction "1_1") (pintype "passive"))
      (node (ref "USB-TYPE C") (pin "A2") (pinfunction "TX1+_A2") (pintype "passive"))
    )
    (net (code "81") (name "Net-(USB-TYPE C-TX1-)") (class "Default")
      (node (ref "C2") (pin "1") (pinfunction "1_1") (pintype "passive"))
      (node (ref "USB-TYPE C") (pin "A3") (pinfunction "TX1-_A3") (pintype "passive"))
    )
    (net (code "82") (name "Net-(USB-TYPE C-TX2+)") (class "Default")
      (node (ref "C6") (pin "1") (pinfunction "1_1") (pintype "passive"))
      (node (ref "USB-TYPE C") (pin "B2") (pinfunction "TX2+_B2") (pintype "passive"))
    )
    (net (code "83") (name "Net-(USB-TYPE C-TX2-)") (class "Default")
      (node (ref "C5") (pin "1") (pinfunction "1_1") (pintype "passive"))
      (node (ref "USB-TYPE C") (pin "B3") (pinfunction "TX2-_B3") (pintype "passive"))
    )
    (net (code "84") (name "VBUS") (class "Default")
      (node (ref "D1") (pin "A") (pinfunction "A_A") (pintype "passive"))
      (node (ref "USB-TYPE C") (pin "A4") (pinfunction "VBUS_A4") (pintype "passive"))
      (node (ref "USB-TYPE C") (pin "A9") (pinfunction "VBUS_A9") (pintype "passive"))
      (node (ref "USB-TYPE C") (pin "B4") (pinfunction "VBUS_B4") (pintype "passive"))
      (node (ref "USB-TYPE C") (pin "B9") (pinfunction "VBUS_B9") (pintype "passive"))
    )
    (net (code "85") (name "VCC12A_RX") (class "Default")
      (node (ref "C28") (pin "1") (pinfunction "1_1") (pintype "passive"))
      (node (ref "C29") (pin "1") (pinfunction "1_1") (pintype "passive"))
      (node (ref "C30") (pin "1") (pinfunction "1_1") (pintype "passive"))
      (node (ref "C31") (pin "1") (pinfunction "1_1") (pintype "passive"))
      (node (ref "C32") (pin "1") (pinfunction "1_1") (pintype "passive"))
      (node (ref "FB7") (pin "2") (pinfunction "2_2") (pintype "passive"))
      (node (ref "U1") (pin "10") (pinfunction "VCC12_PI_10") (pintype "power_in"))
      (node (ref "U1") (pin "13") (pinfunction "VCC12_RXPLL_13") (pintype "power_in"))
      (node (ref "U1") (pin "4") (pinfunction "VCC12A_RX_4") (pintype "power_in"))
    )
    (net (code "86") (name "VCC12D_RX") (class "Default")
      (node (ref "C25") (pin "1") (pinfunction "1_1") (pintype "passive"))
      (node (ref "C26") (pin "1") (pinfunction "1_1") (pintype "passive"))
      (node (ref "C27") (pin "1") (pinfunction "1_1") (pintype "passive"))
      (node (ref "FB8") (pin "2") (pinfunction "2_2") (pintype "passive"))
      (node (ref "U1") (pin "1") (pinfunction "VCC12D_RX_1") (pintype "power_in"))
    )
    (net (code "87") (name "VCC12_TX") (class "Default")
      (node (ref "C33") (pin "1") (pinfunction "1_1") (pintype "passive"))
      (node (ref "C34") (pin "1") (pinfunction "1_1") (pintype "passive"))
      (node (ref "C35") (pin "1") (pinfunction "1_1") (pintype "passive"))
      (node (ref "C36") (pin "1") (pinfunction "1_1") (pintype "passive"))
      (node (ref "C37") (pin "1") (pinfunction "1_1") (pintype "passive"))
      (node (ref "FB6") (pin "2") (pinfunction "2_2") (pintype "passive"))
      (node (ref "U1") (pin "34") (pinfunction "VCC12_TX_34") (pintype "power_in"))
      (node (ref "U1") (pin "46") (pinfunction "VCC12_TX2_46") (pintype "power_in"))
      (node (ref "U1") (pin "48") (pinfunction "VCC12_TX1_48") (pintype "power_in"))
      (node (ref "U1") (pin "59") (pinfunction "VCC12_TX0_59") (pintype "power_in"))
    )
    (net (code "88") (name "VCC33") (class "Default")
      (node (ref "C40") (pin "1") (pinfunction "1_1") (pintype "passive"))
      (node (ref "C41") (pin "1") (pinfunction "1_1") (pintype "passive"))
      (node (ref "C42") (pin "1") (pinfunction "1_1") (pintype "passive"))
      (node (ref "FB1") (pin "1") (pinfunction "1_1") (pintype "passive"))
      (node (ref "FB2") (pin "1") (pinfunction "1_1") (pintype "passive"))
      (node (ref "FB3") (pin "1") (pinfunction "1_1") (pintype "passive"))
      (node (ref "R20") (pin "1") (pinfunction "1_1") (pintype "passive"))
      (node (ref "R7") (pin "1") (pinfunction "1_1") (pintype "passive"))
      (node (ref "R8") (pin "2") (pinfunction "2_2") (pintype "passive"))
      (node (ref "R9") (pin "2") (pinfunction "2_2") (pintype "passive"))
      (node (ref "U2") (pin "2") (pinfunction "OUT_2") (pintype "passive"))
      (node (ref "U2") (pin "4") (pinfunction "OUT_4") (pintype "passive"))
    )
    (net (code "89") (name "VCC33_RX") (class "Default")
      (node (ref "C16") (pin "1") (pinfunction "1_1") (pintype "passive"))
      (node (ref "C17") (pin "1") (pinfunction "1_1") (pintype "passive"))
      (node (ref "C18") (pin "1") (pinfunction "1_1") (pintype "passive"))
      (node (ref "C19") (pin "1") (pinfunction "1_1") (pintype "passive"))
      (node (ref "FB3") (pin "2") (pinfunction "2_2") (pintype "passive"))
      (node (ref "U1") (pin "62") (pinfunction "VCC33_BG_62") (pintype "power_in"))
      (node (ref "U1") (pin "7") (pinfunction "VCC33_RX_7") (pintype "power_in"))
    )
    (net (code "90") (name "VCC33_STM") (class "Default")
      (node (ref "C43") (pin "1") (pinfunction "1_1") (pintype "passive"))
      (node (ref "C50") (pin "2") (pinfunction "2_2") (pintype "passive"))
      (node (ref "C51") (pin "1") (pinfunction "1_1") (pintype "passive"))
      (node (ref "C58") (pin "1") (pinfunction "1_1") (pintype "passive"))
      (node (ref "FB1") (pin "2") (pinfunction "2_2") (pintype "passive"))
      (node (ref "R15") (pin "1") (pinfunction "1_1") (pintype "passive"))
      (node (ref "R17") (pin "2") (pinfunction "2_2") (pintype "passive"))
      (node (ref "R19") (pin "2") (pinfunction "2_2") (pintype "passive"))
      (node (ref "STM32_I2C") (pin "1") (pinfunction "1_1") (pintype "passive"))
      (node (ref "U3") (pin "1") (pinfunction "VBAT_1") (pintype "power_in"))
      (node (ref "U3") (pin "24") (pinfunction "VDD1_24") (pintype "power_in"))
      (node (ref "U3") (pin "36") (pinfunction "VDD2_36") (pintype "power_in"))
      (node (ref "U3") (pin "48") (pinfunction "VDD_48") (pintype "power_in"))
      (node (ref "U3") (pin "9") (pinfunction "VDDA/VREF+_9") (pintype "power_in"))
    )
    (net (code "91") (name "VCC33_TX") (class "Default")
      (node (ref "C10") (pin "1") (pinfunction "1_1") (pintype "passive"))
      (node (ref "C11") (pin "1") (pinfunction "1_1") (pintype "passive"))
      (node (ref "C12") (pin "1") (pinfunction "1_1") (pintype "passive"))
      (node (ref "C13") (pin "1") (pinfunction "1_1") (pintype "passive"))
      (node (ref "C14") (pin "1") (pinfunction "1_1") (pintype "passive"))
      (node (ref "C15") (pin "1") (pinfunction "1_1") (pintype "passive"))
      (node (ref "FB2") (pin "2") (pinfunction "2_2") (pintype "passive"))
      (node (ref "U1") (pin "16") (pinfunction "VCC33_IO_16") (pintype "power_in"))
      (node (ref "U1") (pin "25") (pinfunction "VCC33_IO_25") (pintype "power_in"))
      (node (ref "U1") (pin "33") (pinfunction "VCC33_TX_33") (pintype "power_in"))
      (node (ref "U1") (pin "45") (pinfunction "VCC33_TX2_45") (pintype "power_in"))
      (node (ref "U1") (pin "47") (pinfunction "VCC33_TXPLL_47") (pintype "power_in"))
    )
    (net (code "92") (name "VDD") (class "Default")
      (node (ref "C20") (pin "1") (pinfunction "1_1") (pintype "passive"))
      (node (ref "C21") (pin "1") (pinfunction "1_1") (pintype "passive"))
      (node (ref "C22") (pin "1") (pinfunction "1_1") (pintype "passive"))
      (node (ref "C23") (pin "1") (pinfunction "1_1") (pintype "passive"))
      (node (ref "C24") (pin "1") (pinfunction "1_1") (pintype "passive"))
      (node (ref "FB5") (pin "2") (pinfunction "2_2") (pintype "passive"))
      (node (ref "U1") (pin "24") (pinfunction "VDD_24") (pintype "power_in"))
      (node (ref "U1") (pin "30") (pinfunction "VDD_30") (pintype "power_in"))
      (node (ref "U1") (pin "60") (pinfunction "VDD_60") (pintype "power_in"))
    )
    (net (code "93") (name "unconnected-(Laser Display CON-NC-Pad4)") (class "Default")
      (node (ref "Laser Display CON") (pin "4") (pinfunction "NC_4") (pintype "passive"))
    )
    (net (code "94") (name "unconnected-(Laser Display CON-NC-Pad5)") (class "Default")
      (node (ref "Laser Display CON") (pin "5") (pinfunction "NC_5") (pintype "passive"))
    )
    (net (code "95") (name "unconnected-(Laser Display CON-TEST1-Pad6)") (class "Default")
      (node (ref "Laser Display CON") (pin "6") (pinfunction "TEST1_6") (pintype "passive"))
    )
    (net (code "96") (name "unconnected-(Laser Display CON-TEST2-Pad10)") (class "Default")
      (node (ref "Laser Display CON") (pin "10") (pinfunction "TEST2_10") (pintype "passive"))
    )
    (net (code "97") (name "unconnected-(Laser Display CON-TEST3-Pad11)") (class "Default")
      (node (ref "Laser Display CON") (pin "11") (pinfunction "TEST3_11") (pintype "passive"))
    )
    (net (code "98") (name "unconnected-(Laser Display CON-TEST4-Pad13)") (class "Default")
      (node (ref "Laser Display CON") (pin "13") (pinfunction "TEST4_13") (pintype "passive"))
    )
    (net (code "99") (name "unconnected-(Laser Display CON-TEST5-Pad14)") (class "Default")
      (node (ref "Laser Display CON") (pin "14") (pinfunction "TEST5_14") (pintype "passive"))
    )
    (net (code "100") (name "unconnected-(U1-RX_HPD-Pad23)") (class "Default")
      (node (ref "U1") (pin "23") (pinfunction "RX_HPD_23") (pintype "output"))
    )
    (net (code "101") (name "unconnected-(U3-NRST-Pad7)") (class "Default")
      (node (ref "U3") (pin "7") (pinfunction "NRST_7") (pintype "power_in"))
    )
    (net (code "102") (name "unconnected-(U3-PA0{slash}WKUP-Pad10)") (class "Default")
      (node (ref "U3") (pin "10") (pinfunction "PA0/WKUP_10") (pintype "power_in"))
    )
    (net (code "103") (name "unconnected-(U3-PA1-Pad11)") (class "Default")
      (node (ref "U3") (pin "11") (pinfunction "PA1_11") (pintype "power_in"))
    )
    (net (code "104") (name "unconnected-(U3-PA3-Pad13)") (class "Default")
      (node (ref "U3") (pin "13") (pinfunction "PA3_13") (pintype "power_in"))
    )
    (net (code "105") (name "unconnected-(U3-PA4-Pad14)") (class "Default")
      (node (ref "U3") (pin "14") (pinfunction "PA4_14") (pintype "power_in"))
    )
    (net (code "106") (name "unconnected-(U3-PA5-Pad15)") (class "Default")
      (node (ref "U3") (pin "15") (pinfunction "PA5_15") (pintype "power_in"))
    )
    (net (code "107") (name "unconnected-(U3-PA6-Pad16)") (class "Default")
      (node (ref "U3") (pin "16") (pinfunction "PA6_16") (pintype "power_in"))
    )
    (net (code "108") (name "unconnected-(U3-PA7-Pad17)") (class "Default")
      (node (ref "U3") (pin "17") (pinfunction "PA7_17") (pintype "power_in"))
    )
    (net (code "109") (name "unconnected-(U3-PA8-Pad29)") (class "Default")
      (node (ref "U3") (pin "29") (pinfunction "PA8_29") (pintype "power_in"))
    )
    (net (code "110") (name "unconnected-(U3-PA11-Pad32)") (class "Default")
      (node (ref "U3") (pin "32") (pinfunction "PA11_32") (pintype "power_in"))
    )
    (net (code "111") (name "unconnected-(U3-PA15-Pad38)") (class "Default")
      (node (ref "U3") (pin "38") (pinfunction "PA15_38") (pintype "power_in"))
    )
    (net (code "112") (name "unconnected-(U3-PB2-Pad20)") (class "Default")
      (node (ref "U3") (pin "20") (pinfunction "PB2_20") (pintype "power_in"))
    )
    (net (code "113") (name "unconnected-(U3-PB3-Pad39)") (class "Default")
      (node (ref "U3") (pin "39") (pinfunction "PB3_39") (pintype "power_in"))
    )
    (net (code "114") (name "unconnected-(U3-PB4-Pad40)") (class "Default")
      (node (ref "U3") (pin "40") (pinfunction "PB4_40") (pintype "power_in"))
    )
    (net (code "115") (name "unconnected-(U3-PB5-Pad41)") (class "Default")
      (node (ref "U3") (pin "41") (pinfunction "PB5_41") (pintype "power_in"))
    )
    (net (code "116") (name "unconnected-(U3-PB6-Pad42)") (class "Default")
      (node (ref "U3") (pin "42") (pinfunction "PB6_42") (pintype "power_in"))
    )
    (net (code "117") (name "unconnected-(U3-PB7-Pad43)") (class "Default")
      (node (ref "U3") (pin "43") (pinfunction "PB7_43") (pintype "power_in"))
    )
    (net (code "118") (name "unconnected-(U3-PB8-Pad45)") (class "Default")
      (node (ref "U3") (pin "45") (pinfunction "PB8_45") (pintype "power_in"))
    )
    (net (code "119") (name "unconnected-(U3-PB9-Pad46)") (class "Default")
      (node (ref "U3") (pin "46") (pinfunction "PB9_46") (pintype "power_in"))
    )
    (net (code "120") (name "unconnected-(U3-PC14-Pad3)") (class "Default")
      (node (ref "U3") (pin "3") (pinfunction "PC14_3") (pintype "power_in"))
    )
    (net (code "121") (name "unconnected-(U3-PC15-Pad4)") (class "Default")
      (node (ref "U3") (pin "4") (pinfunction "PC15_4") (pintype "power_in"))
    )
    (net (code "122") (name "unconnected-(USB-TYPE C-NC1-Pad5)") (class "Default")
      (node (ref "USB-TYPE C") (pin "5") (pinfunction "NC1_5") (pintype "passive"))
    )
    (net (code "123") (name "unconnected-(USB-TYPE C-NC2-Pad6)") (class "Default")
      (node (ref "USB-TYPE C") (pin "6") (pinfunction "NC2_6") (pintype "passive"))
    )
  )
)
